# analog_out_test.net
KiCad netlist of a schematic drawn in EAGLE
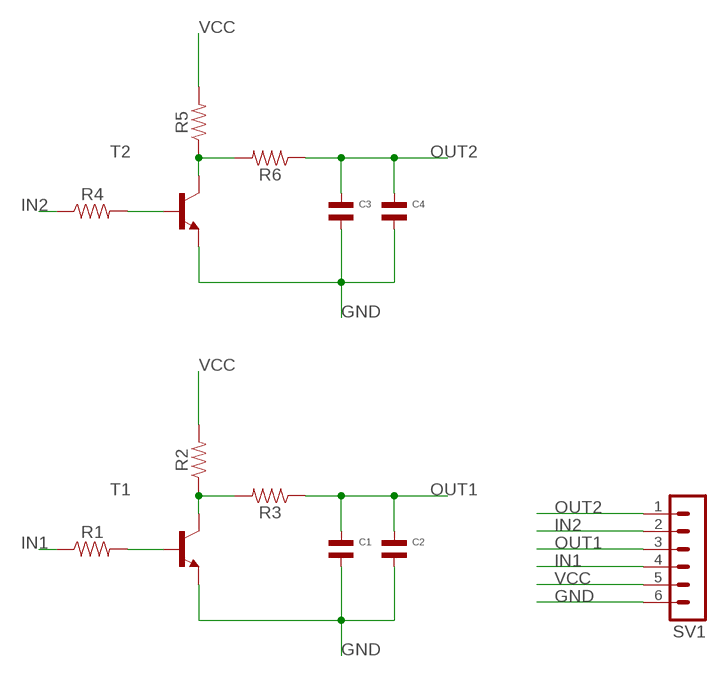
[diagram p0: schematic, sheet 1]

(export (version "E")
  (design (tool "Eeschema 10.0.6"))
  (components
    (comp (ref "C1")
      (value "CAPACITOR_NP_1206")
      (footprint "eagle-import:C1206")
      (libsource (lib "eagle-import") (part "CAPACITOR_NP_1206"))
    )
    (comp (ref "C2")
      (value "CAPACITOR_NP_1206")
      (footprint "eagle-import:C1206")
      (libsource (lib "eagle-import") (part "CAPACITOR_NP_1206"))
    )
    (comp (ref "C3")
      (value "CAPACITOR_NP_1206")
      (footprint "eagle-import:C1206")
      (libsource (lib "eagle-import") (part "CAPACITOR_NP_1206"))
    )
    (comp (ref "C4")
      (value "CAPACITOR_NP_1206")
      (footprint "eagle-import:C1206")
      (libsource (lib "eagle-import") (part "CAPACITOR_NP_1206"))
    )
    (comp (ref "R1")
      (value "RESISTOR21206")
      (footprint "eagle-import:1206")
      (libsource (lib "eagle-import") (part "RESISTOR21206"))
    )
    (comp (ref "R2")
      (value "RESISTOR21206")
      (footprint "eagle-import:1206")
      (libsource (lib "eagle-import") (part "RESISTOR21206"))
    )
    (comp (ref "R3")
      (value "RESISTOR21206")
      (footprint "eagle-import:1206")
      (libsource (lib "eagle-import") (part "RESISTOR21206"))
    )
    (comp (ref "R4")
      (value "RESISTOR21206")
      (footprint "eagle-import:1206")
      (libsource (lib "eagle-import") (part "RESISTOR21206"))
    )
    (comp (ref "R5")
      (value "RESISTOR21206")
      (footprint "eagle-import:1206")
      (libsource (lib "eagle-import") (part "RESISTOR21206"))
    )
    (comp (ref "R6")
      (value "RESISTOR21206")
      (footprint "eagle-import:1206")
      (libsource (lib "eagle-import") (part "RESISTOR21206"))
    )
    (comp (ref "SV1")
      (value "MA06-1")
      (footprint "eagle-import:MA06-1")
      (libsource (lib "eagle-import") (part "MA06-1"))
    )
    (comp (ref "T1")
      (value "BC849-NPN-SOT23-BEC")
      (footprint "eagle-import:SOT23-BEC")
      (libsource (lib "eagle-import") (part "-NPN-SOT23-BECBC849"))
    )
    (comp (ref "T2")
      (value "BC849-NPN-SOT23-BEC")
      (footprint "eagle-import:SOT23-BEC")
      (libsource (lib "eagle-import") (part "-NPN-SOT23-BECBC849"))
    )
  )
  (nets
    (net (code "1") (name "/GND") (class "Default")
      (node (ref "C1") (pin "P$2") (pinfunction "P$2_P$2") (pintype "passive"))
      (node (ref "C2") (pin "P$2") (pinfunction "P$2_P$2") (pintype "passive"))
      (node (ref "C3") (pin "P$2") (pinfunction "P$2_P$2") (pintype "passive"))
      (node (ref "C4") (pin "P$2") (pinfunction "P$2_P$2") (pintype "passive"))
      (node (ref "SV1") (pin "6") (pinfunction "6_6") (pintype "passive"))
      (node (ref "T1") (pin "E") (pinfunction "E_E") (pintype "passive"))
      (node (ref "T2") (pin "E") (pinfunction "E_E") (pintype "passive"))
    )
    (net (code "2") (name "/IN1") (class "Default")
      (node (ref "R1") (pin "1") (pinfunction "1_1") (pintype "passive"))
      (node (ref "SV1") (pin "4") (pinfunction "4_4") (pintype "passive"))
    )
    (net (code "3") (name "/IN2") (class "Default")
      (node (ref "R4") (pin "1") (pinfunction "1_1") (pintype "passive"))
      (node (ref "SV1") (pin "2") (pinfunction "2_2") (pintype "passive"))
    )
    (net (code "4") (name "/OUT1") (class "Default")
      (node (ref "C1") (pin "P$1") (pinfunction "P$1_P$1") (pintype "passive"))
      (node (ref "C2") (pin "P$1") (pinfunction "P$1_P$1") (pintype "passive"))
      (node (ref "R3") (pin "1") (pinfunction "1_1") (pintype "passive"))
      (node (ref "SV1") (pin "3") (pinfunction "3_3") (pintype "passive"))
    )
    (net (code "5") (name "/OUT2") (class "Default")
      (node (ref "C3") (pin "P$1") (pinfunction "P$1_P$1") (pintype "passive"))
      (node (ref "C4") (pin "P$1") (pinfunction "P$1_P$1") (pintype "passive"))
      (node (ref "R6") (pin "1") (pinfunction "1_1") (pintype "passive"))
      (node (ref "SV1") (pin "1") (pinfunction "1_1") (pintype "passive"))
    )
    (net (code "6") (name "/VCC") (class "Default")
      (node (ref "R2") (pin "2") (pinfunction "2_2") (pintype "passive"))
      (node (ref "R5") (pin "2") (pinfunction "2_2") (pintype "passive"))
      (node (ref "SV1") (pin "5") (pinfunction "5_5") (pintype "passive"))
    )
    (net (code "7") (name "Net-(R1-Pad2)") (class "Default")
      (node (ref "R1") (pin "2") (pinfunction "2_2") (pintype "passive"))
      (node (ref "T1") (pin "B") (pinfunction "B_B") (pintype "passive"))
    )
    (net (code "8") (name "Net-(R2-Pad1)") (class "Default")
      (node (ref "R2") (pin "1") (pinfunction "1_1") (pintype "passive"))
      (node (ref "R3") (pin "2") (pinfunction "2_2") (pintype "passive"))
      (node (ref "T1") (pin "C") (pinfunction "C_C") (pintype "passive"))
    )
    (net (code "9") (name "Net-(R4-Pad2)") (class "Default")
      (node (ref "R4") (pin "2") (pinfunction "2_2") (pintype "passive"))
      (node (ref "T2") (pin "B") (pinfunction "B_B") (pintype "passive"))
    )
    (net (code "10") (name "Net-(R5-Pad1)") (class "Default")
      (node (ref "R5") (pin "1") (pinfunction "1_1") (pintype "passive"))
      (node (ref "R6") (pin "2") (pinfunction "2_2") (pintype "passive"))
      (node (ref "T2") (pin "C") (pinfunction "C_C") (pintype "passive"))
    )
  )
)
